# design.net
KiCad netlist of a schematic drawn in Altium Designer
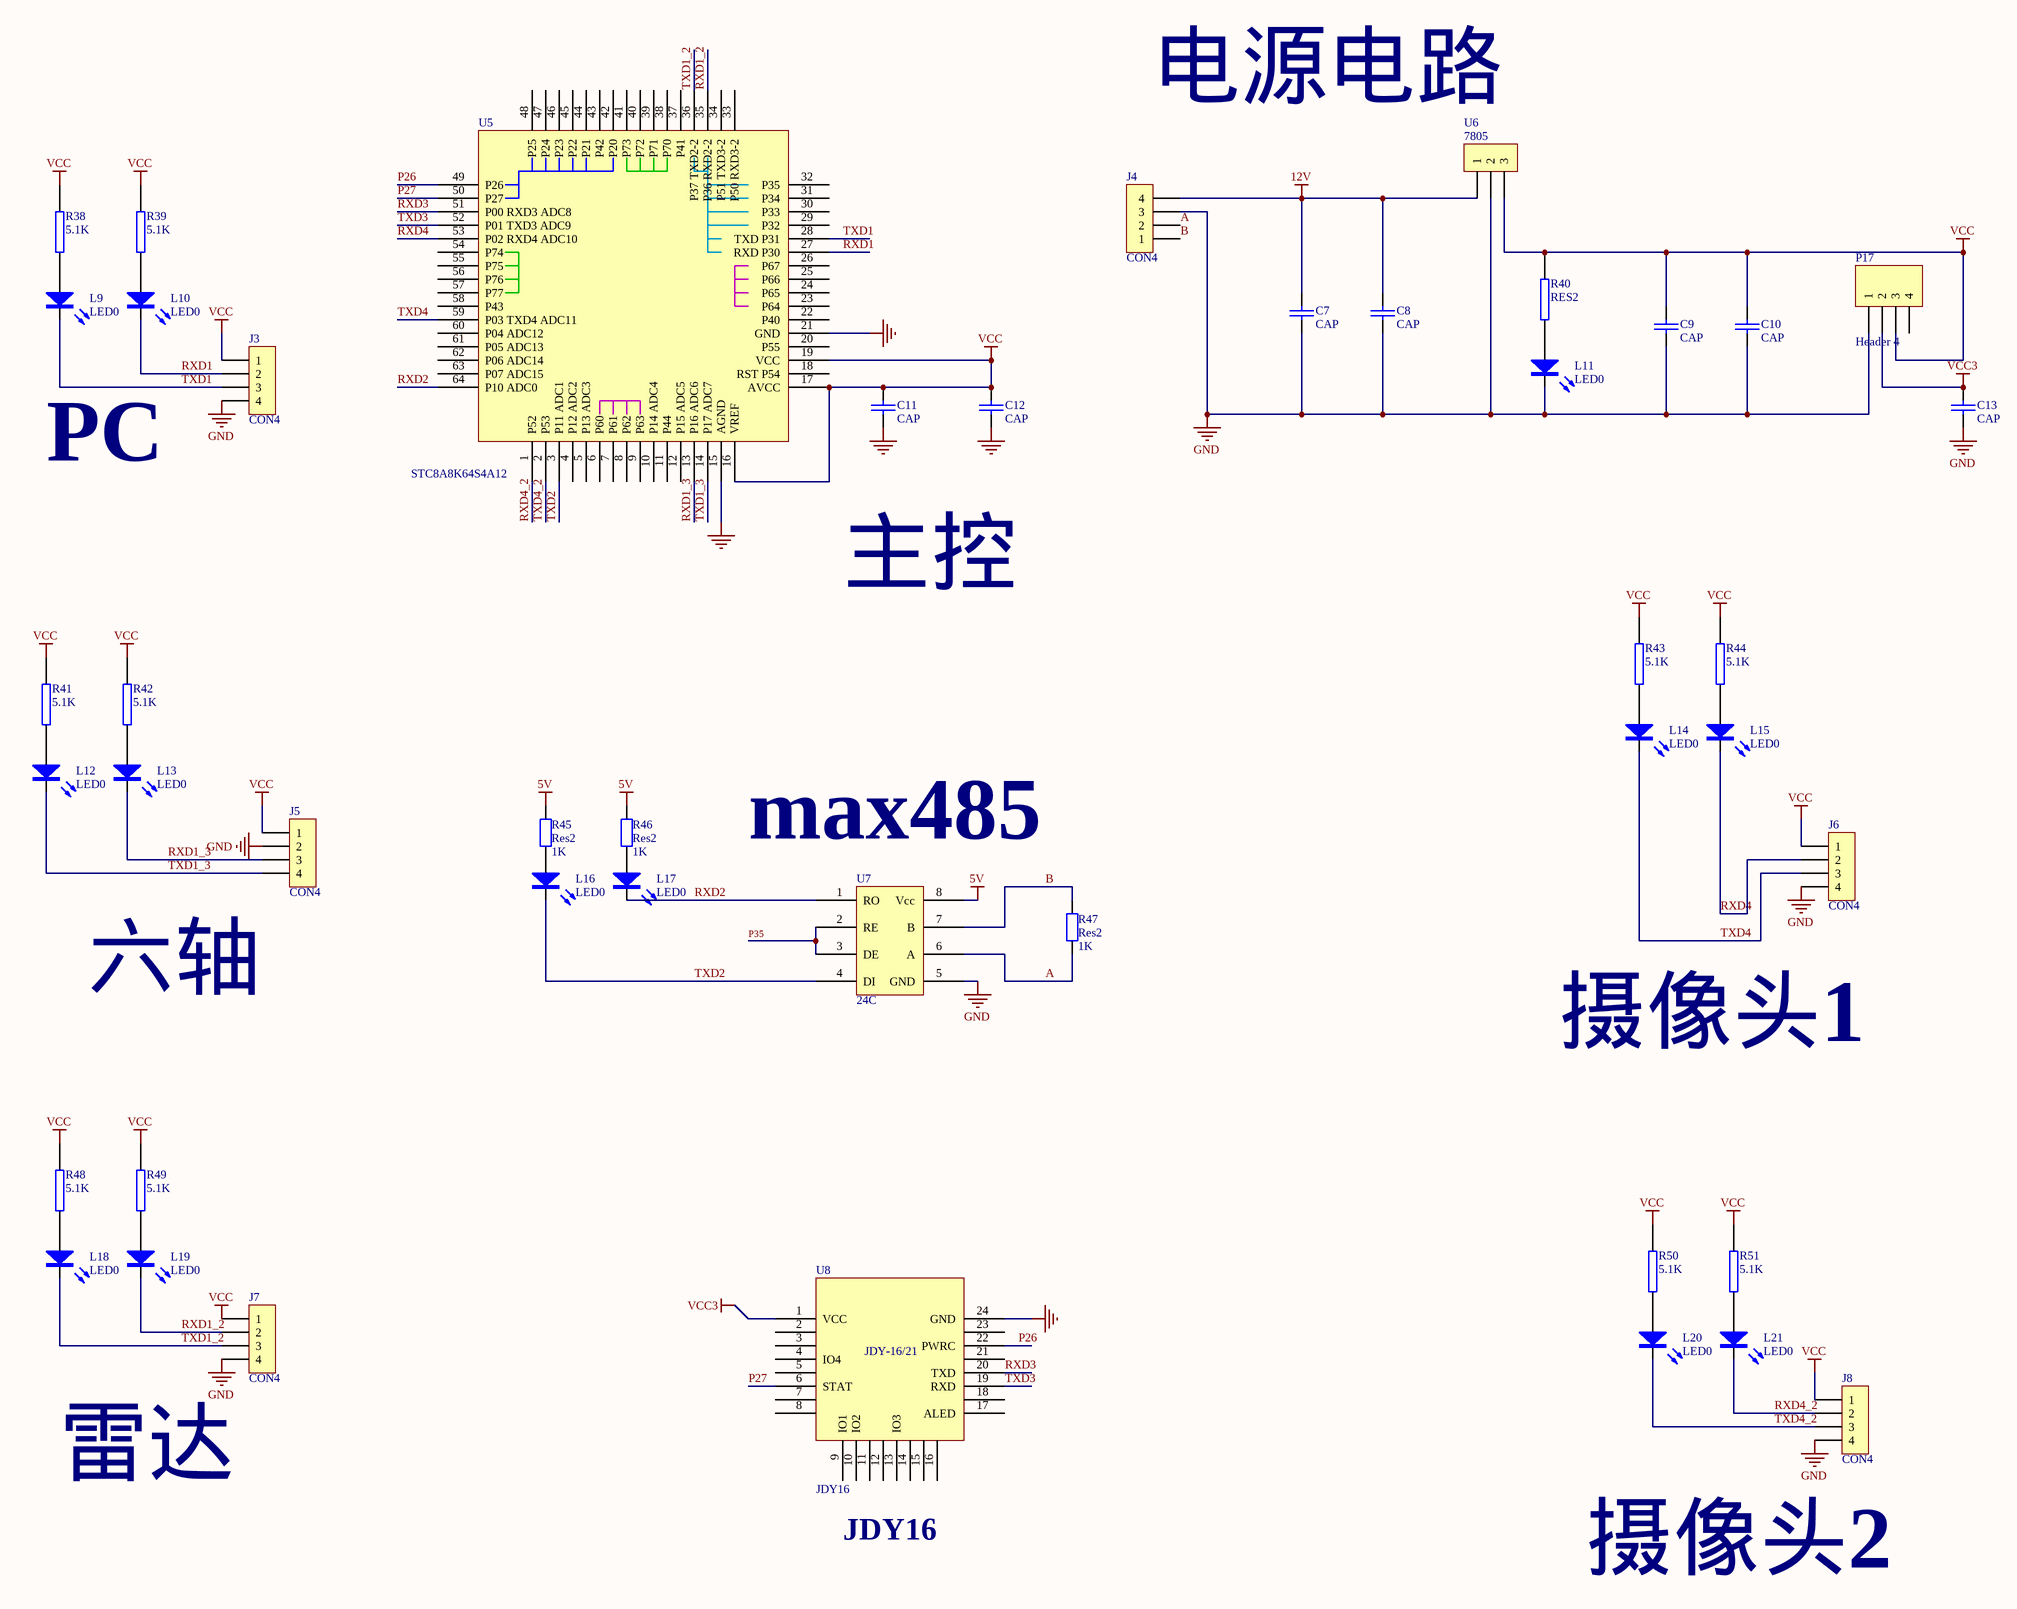
[diagram p0: 扫描仪.SchDoc]

(export (version "E")
  (design (tool "Eeschema 10.0.6"))
  (components
    (comp (ref "C7")
      (value "CAP")
      (footprint "0805_L")
      (description "Capacitor")
      (libsource (lib "*") (part "CAP"))
    )
    (comp (ref "C8")
      (value "CAP")
      (footprint "1206_L")
      (description "Capacitor")
      (libsource (lib "*") (part "CAP"))
    )
    (comp (ref "C9")
      (value "CAP")
      (footprint "0805_L")
      (description "Capacitor")
      (libsource (lib "*") (part "CAP"))
    )
    (comp (ref "C10")
      (value "CAP")
      (footprint "1206_L")
      (description "Capacitor")
      (libsource (lib "*") (part "CAP"))
    )
    (comp (ref "C11")
      (value "CAP")
      (footprint "0805_L")
      (description "Capacitor")
      (libsource (lib "*") (part "CAP"))
    )
    (comp (ref "C12")
      (value "CAP")
      (footprint "0805_L")
      (description "Capacitor")
      (libsource (lib "*") (part "CAP"))
    )
    (comp (ref "C13")
      (value "CAP")
      (footprint "0805_L")
      (description "Capacitor")
      (libsource (lib "*") (part "CAP"))
    )
    (comp (ref "J3")
      (value "CON4")
      (footprint "SP4")
      (description "Connector")
      (libsource (lib "*") (part "CON4"))
    )
    (comp (ref "J4")
      (value "CON4")
      (footprint "SP4")
      (description "Connector")
      (libsource (lib "") (part "CON4_1"))
    )
    (comp (ref "J5")
      (value "CON4")
      (footprint "SP4")
      (description "Connector")
      (libsource (lib "*") (part "CON4"))
    )
    (comp (ref "J6")
      (value "CON4")
      (footprint "SP4")
      (description "Connector")
      (libsource (lib "*") (part "CON4"))
    )
    (comp (ref "J7")
      (value "CON4")
      (footprint "SP4")
      (description "Connector")
      (libsource (lib "*") (part "CON4"))
    )
    (comp (ref "J8")
      (value "CON4")
      (footprint "SP4")
      (description "Connector")
      (libsource (lib "*") (part "CON4"))
    )
    (comp (ref "L9")
      (value "LED0")
      (footprint "TPLED")
      (description "light Emitting Diode")
      (libsource (lib "*") (part "LED0"))
    )
    (comp (ref "L10")
      (value "LED0")
      (footprint "TPLED")
      (description "light Emitting Diode")
      (libsource (lib "*") (part "LED0"))
    )
    (comp (ref "L11")
      (value "LED0")
      (footprint "TPLED")
      (description "light Emitting Diode")
      (libsource (lib "*") (part "LED0"))
    )
    (comp (ref "L12")
      (value "LED0")
      (footprint "TPLED")
      (description "light Emitting Diode")
      (libsource (lib "*") (part "LED0"))
    )
    (comp (ref "L13")
      (value "LED0")
      (footprint "TPLED")
      (description "light Emitting Diode")
      (libsource (lib "*") (part "LED0"))
    )
    (comp (ref "L14")
      (value "LED0")
      (footprint "TPLED")
      (description "light Emitting Diode")
      (libsource (lib "*") (part "LED0"))
    )
    (comp (ref "L15")
      (value "LED0")
      (footprint "TPLED")
      (description "light Emitting Diode")
      (libsource (lib "*") (part "LED0"))
    )
    (comp (ref "L16")
      (value "LED0")
      (footprint "TPLED")
      (description "light Emitting Diode")
      (libsource (lib "*") (part "LED0"))
    )
    (comp (ref "L17")
      (value "LED0")
      (footprint "TPLED")
      (description "light Emitting Diode")
      (libsource (lib "*") (part "LED0"))
    )
    (comp (ref "L18")
      (value "LED0")
      (footprint "TPLED")
      (description "light Emitting Diode")
      (libsource (lib "*") (part "LED0"))
    )
    (comp (ref "L19")
      (value "LED0")
      (footprint "TPLED")
      (description "light Emitting Diode")
      (libsource (lib "*") (part "LED0"))
    )
    (comp (ref "L20")
      (value "LED0")
      (footprint "TPLED")
      (description "light Emitting Diode")
      (libsource (lib "*") (part "LED0"))
    )
    (comp (ref "L21")
      (value "LED0")
      (footprint "TPLED")
      (description "light Emitting Diode")
      (libsource (lib "*") (part "LED0"))
    )
    (comp (ref "P17")
      (value "Header 4")
      (footprint "1117")
      (description "Header, 4-Pin")
      (fields (field (name "PUBLISHER") "Altium Limited"))
      (libsource (lib "Miscellaneous Connectors") (part "Header 4"))
    )
    (comp (ref "R38") (value "5.1K") (footprint "0805_L") (libsource (lib "*") (part "RES2")))
    (comp (ref "R39") (value "5.1K") (footprint "0805_L") (libsource (lib "*") (part "RES2")))
    (comp (ref "R40") (value "RES2") (footprint "0805_L") (libsource (lib "*") (part "RES2")))
    (comp (ref "R41") (value "5.1K") (footprint "0805_L") (libsource (lib "*") (part "RES2")))
    (comp (ref "R42") (value "5.1K") (footprint "0805_L") (libsource (lib "*") (part "RES2")))
    (comp (ref "R43") (value "5.1K") (footprint "0805_L") (libsource (lib "*") (part "RES2")))
    (comp (ref "R44") (value "5.1K") (footprint "0805_L") (libsource (lib "*") (part "RES2")))
    (comp (ref "R45")
      (value "Res2")
      (footprint "0805_R")
      (description "Resistor")
      (fields (field (name "ALTIUM_VALUE") "1K") (field (name "PUBLISHER") "Altium Limited"))
      (libsource (lib "Miscellaneous Devices") (part "Res2"))
    )
    (comp (ref "R46")
      (value "Res2")
      (footprint "0805_R")
      (description "Resistor")
      (fields (field (name "ALTIUM_VALUE") "1K") (field (name "PUBLISHER") "Altium Limited"))
      (libsource (lib "Miscellaneous Devices") (part "Res2"))
    )
    (comp (ref "R47")
      (value "Res2")
      (footprint "0805_R")
      (description "Resistor")
      (fields (field (name "ALTIUM_VALUE") "1K") (field (name "PUBLISHER") "Altium Limited"))
      (libsource (lib "Miscellaneous Devices") (part "Res2"))
    )
    (comp (ref "R48") (value "5.1K") (footprint "0805_L") (libsource (lib "*") (part "RES2")))
    (comp (ref "R49") (value "5.1K") (footprint "0805_L") (libsource (lib "*") (part "RES2")))
    (comp (ref "R50") (value "5.1K") (footprint "0805_L") (libsource (lib "*") (part "RES2")))
    (comp (ref "R51") (value "5.1K") (footprint "0805_L") (libsource (lib "*") (part "RES2")))
    (comp (ref "U5") (value "STC8A8K64S4A12") (footprint "LQFP64S") (libsource (lib "*") (part "STC64")))
    (comp (ref "U6")
      (value "7805")
      (footprint "TO252")
      (description "Connector")
      (libsource (lib "*") (part "CON3"))
    )
    (comp (ref "U7") (value "24C") (footprint "SOP8") (libsource (lib "*") (part "24C")))
    (comp (ref "U8") (value "JDY16") (footprint "JDY16") (libsource (lib "stc64") (part "JDY21")))
  )
  (nets
    (net (code "1") (name "/A") (class "Default")
      (node (ref "J4") (pin "2") (pinfunction "2_2") (pintype "passive"))
      (node (ref "R47") (pin "1") (pinfunction "1_1") (pintype "passive"))
      (node (ref "U7") (pin "6") (pinfunction "A_6") (pintype "passive"))
    )
    (net (code "2") (name "/B") (class "Default")
      (node (ref "J4") (pin "1") (pinfunction "1_1") (pintype "passive"))
      (node (ref "R47") (pin "2") (pinfunction "2_2") (pintype "passive"))
      (node (ref "U7") (pin "7") (pinfunction "B_7") (pintype "passive"))
    )
    (net (code "3") (name "/P26") (class "Default")
      (node (ref "U5") (pin "49") (pinfunction "P26_49") (pintype "passive"))
      (node (ref "U8") (pin "22") (pinfunction "PWRC_22") (pintype "passive"))
    )
    (net (code "4") (name "/P27") (class "Default")
      (node (ref "U5") (pin "50") (pinfunction "P27_50") (pintype "passive"))
      (node (ref "U8") (pin "6") (pinfunction "STAT_6") (pintype "passive"))
    )
    (net (code "5") (name "/P35") (class "Default")
      (node (ref "U7") (pin "2") (pinfunction "RE_2") (pintype "passive"))
      (node (ref "U7") (pin "3") (pinfunction "DE_3") (pintype "passive"))
    )
    (net (code "6") (name "/RXD1") (class "Default")
      (node (ref "J3") (pin "2") (pinfunction "2_2") (pintype "passive"))
      (node (ref "L10") (pin "2") (pinfunction "K_2") (pintype "passive"))
      (node (ref "U5") (pin "27") (pinfunction "RXD_P30_27") (pintype "passive"))
    )
    (net (code "7") (name "/RXD1_2") (class "Default")
      (node (ref "J7") (pin "2") (pinfunction "2_2") (pintype "passive"))
      (node (ref "L19") (pin "2") (pinfunction "K_2") (pintype "passive"))
      (node (ref "U5") (pin "35") (pinfunction "P36_RXD2-2_35") (pintype "passive"))
    )
    (net (code "8") (name "/RXD1_3") (class "Default")
      (node (ref "J5") (pin "3") (pinfunction "3_3") (pintype "passive"))
      (node (ref "L13") (pin "2") (pinfunction "K_2") (pintype "passive"))
      (node (ref "U5") (pin "13") (pinfunction "P16_ADC6_13") (pintype "passive"))
    )
    (net (code "9") (name "/RXD2") (class "Default")
      (node (ref "L17") (pin "2") (pinfunction "K_2") (pintype "passive"))
      (node (ref "U5") (pin "64") (pinfunction "P10_ADC0_64") (pintype "passive"))
      (node (ref "U7") (pin "1") (pinfunction "RO_1") (pintype "passive"))
    )
    (net (code "10") (name "/RXD3") (class "Default")
      (node (ref "U5") (pin "51") (pinfunction "P00_RXD3_ADC8_51") (pintype "passive"))
      (node (ref "U8") (pin "20") (pinfunction "TXD_20") (pintype "passive"))
    )
    (net (code "11") (name "/RXD4") (class "Default")
      (node (ref "J6") (pin "2") (pinfunction "2_2") (pintype "passive"))
      (node (ref "L15") (pin "2") (pinfunction "K_2") (pintype "passive"))
      (node (ref "U5") (pin "53") (pinfunction "P02_RXD4_ADC10_53") (pintype "passive"))
    )
    (net (code "12") (name "/RXD4_2") (class "Default")
      (node (ref "J8") (pin "2") (pinfunction "2_2") (pintype "passive"))
      (node (ref "L21") (pin "2") (pinfunction "K_2") (pintype "passive"))
      (node (ref "U5") (pin "1") (pinfunction "P52_1") (pintype "passive"))
    )
    (net (code "13") (name "/TXD1") (class "Default")
      (node (ref "J3") (pin "3") (pinfunction "3_3") (pintype "passive"))
      (node (ref "L9") (pin "2") (pinfunction "K_2") (pintype "passive"))
      (node (ref "U5") (pin "28") (pinfunction "TXD_P31_28") (pintype "passive"))
    )
    (net (code "14") (name "/TXD1_2") (class "Default")
      (node (ref "J7") (pin "3") (pinfunction "3_3") (pintype "passive"))
      (node (ref "L18") (pin "2") (pinfunction "K_2") (pintype "passive"))
      (node (ref "U5") (pin "36") (pinfunction "P37_TXD2-2_36") (pintype "passive"))
    )
    (net (code "15") (name "/TXD1_3") (class "Default")
      (node (ref "J5") (pin "4") (pinfunction "4_4") (pintype "passive"))
      (node (ref "L12") (pin "2") (pinfunction "K_2") (pintype "passive"))
      (node (ref "U5") (pin "14") (pinfunction "P17_ADC7_14") (pintype "passive"))
    )
    (net (code "16") (name "/TXD2") (class "Default")
      (node (ref "L16") (pin "2") (pinfunction "K_2") (pintype "passive"))
      (node (ref "U5") (pin "3") (pinfunction "P11_ADC1_3") (pintype "passive"))
      (node (ref "U7") (pin "4") (pinfunction "DI_4") (pintype "passive"))
    )
    (net (code "17") (name "/TXD3") (class "Default")
      (node (ref "U5") (pin "52") (pinfunction "P01_TXD3_ADC9_52") (pintype "passive"))
      (node (ref "U8") (pin "19") (pinfunction "RXD_19") (pintype "passive"))
    )
    (net (code "18") (name "/TXD4") (class "Default")
      (node (ref "J6") (pin "3") (pinfunction "3_3") (pintype "passive"))
      (node (ref "L14") (pin "2") (pinfunction "K_2") (pintype "passive"))
      (node (ref "U5") (pin "59") (pinfunction "P03_TXD4_ADC11_59") (pintype "passive"))
    )
    (net (code "19") (name "/TXD4_2") (class "Default")
      (node (ref "J8") (pin "3") (pinfunction "3_3") (pintype "passive"))
      (node (ref "L20") (pin "2") (pinfunction "K_2") (pintype "passive"))
      (node (ref "U5") (pin "2") (pinfunction "P53_2") (pintype "passive"))
    )
    (net (code "20") (name "5V") (class "Default")
      (node (ref "R45") (pin "2") (pinfunction "2_2") (pintype "passive"))
      (node (ref "R46") (pin "2") (pinfunction "2_2") (pintype "passive"))
      (node (ref "U7") (pin "8") (pinfunction "Vcc_8") (pintype "passive"))
    )
    (net (code "21") (name "12V") (class "Default")
      (node (ref "C7") (pin "1") (pinfunction "1_1") (pintype "passive"))
      (node (ref "C8") (pin "1") (pinfunction "1_1") (pintype "passive"))
      (node (ref "J4") (pin "4") (pinfunction "4_4") (pintype "passive"))
      (node (ref "U6") (pin "1") (pinfunction "1_1") (pintype "passive"))
    )
    (net (code "22") (name "GND") (class "Default")
      (node (ref "C10") (pin "2") (pinfunction "2_2") (pintype "passive"))
      (node (ref "C11") (pin "2") (pinfunction "2_2") (pintype "passive"))
      (node (ref "C12") (pin "2") (pinfunction "2_2") (pintype "passive"))
      (node (ref "C13") (pin "2") (pinfunction "2_2") (pintype "passive"))
      (node (ref "C7") (pin "2") (pinfunction "2_2") (pintype "passive"))
      (node (ref "C8") (pin "2") (pinfunction "2_2") (pintype "passive"))
      (node (ref "C9") (pin "2") (pinfunction "2_2") (pintype "passive"))
      (node (ref "J3") (pin "4") (pinfunction "4_4") (pintype "passive"))
      (node (ref "J4") (pin "3") (pinfunction "3_3") (pintype "passive"))
      (node (ref "J5") (pin "2") (pinfunction "2_2") (pintype "passive"))
      (node (ref "J6") (pin "4") (pinfunction "4_4") (pintype "passive"))
      (node (ref "J7") (pin "4") (pinfunction "4_4") (pintype "passive"))
      (node (ref "J8") (pin "4") (pinfunction "4_4") (pintype "passive"))
      (node (ref "L11") (pin "2") (pinfunction "K_2") (pintype "passive"))
      (node (ref "P17") (pin "1") (pinfunction "1_1") (pintype "passive"))
      (node (ref "U5") (pin "15") (pinfunction "AGND_15") (pintype "passive"))
      (node (ref "U5") (pin "21") (pinfunction "GND_21") (pintype "passive"))
      (node (ref "U6") (pin "2") (pinfunction "2_2") (pintype "passive"))
      (node (ref "U7") (pin "5") (pinfunction "GND_5") (pintype "passive"))
      (node (ref "U8") (pin "24") (pinfunction "GND_24") (pintype "passive"))
    )
    (net (code "23") (name "Net-(L9-A)") (class "Default")
      (node (ref "L9") (pin "1") (pinfunction "A_1") (pintype "passive"))
      (node (ref "R38") (pin "1") (pinfunction "1_1") (pintype "passive"))
    )
    (net (code "24") (name "Net-(L10-A)") (class "Default")
      (node (ref "L10") (pin "1") (pinfunction "A_1") (pintype "passive"))
      (node (ref "R39") (pin "1") (pinfunction "1_1") (pintype "passive"))
    )
    (net (code "25") (name "Net-(L11-A)") (class "Default")
      (node (ref "L11") (pin "1") (pinfunction "A_1") (pintype "passive"))
      (node (ref "R40") (pin "1") (pinfunction "1_1") (pintype "passive"))
    )
    (net (code "26") (name "Net-(L12-A)") (class "Default")
      (node (ref "L12") (pin "1") (pinfunction "A_1") (pintype "passive"))
      (node (ref "R41") (pin "1") (pinfunction "1_1") (pintype "passive"))
    )
    (net (code "27") (name "Net-(L13-A)") (class "Default")
      (node (ref "L13") (pin "1") (pinfunction "A_1") (pintype "passive"))
      (node (ref "R42") (pin "1") (pinfunction "1_1") (pintype "passive"))
    )
    (net (code "28") (name "Net-(L14-A)") (class "Default")
      (node (ref "L14") (pin "1") (pinfunction "A_1") (pintype "passive"))
      (node (ref "R43") (pin "1") (pinfunction "1_1") (pintype "passive"))
    )
    (net (code "29") (name "Net-(L15-A)") (class "Default")
      (node (ref "L15") (pin "1") (pinfunction "A_1") (pintype "passive"))
      (node (ref "R44") (pin "1") (pinfunction "1_1") (pintype "passive"))
    )
    (net (code "30") (name "Net-(L16-A)") (class "Default")
      (node (ref "L16") (pin "1") (pinfunction "A_1") (pintype "passive"))
      (node (ref "R45") (pin "1") (pinfunction "1_1") (pintype "passive"))
    )
    (net (code "31") (name "Net-(L17-A)") (class "Default")
      (node (ref "L17") (pin "1") (pinfunction "A_1") (pintype "passive"))
      (node (ref "R46") (pin "1") (pinfunction "1_1") (pintype "passive"))
    )
    (net (code "32") (name "Net-(L18-A)") (class "Default")
      (node (ref "L18") (pin "1") (pinfunction "A_1") (pintype "passive"))
      (node (ref "R48") (pin "1") (pinfunction "1_1") (pintype "passive"))
    )
    (net (code "33") (name "Net-(L19-A)") (class "Default")
      (node (ref "L19") (pin "1") (pinfunction "A_1") (pintype "passive"))
      (node (ref "R49") (pin "1") (pinfunction "1_1") (pintype "passive"))
    )
    (net (code "34") (name "Net-(L20-A)") (class "Default")
      (node (ref "L20") (pin "1") (pinfunction "A_1") (pintype "passive"))
      (node (ref "R50") (pin "1") (pinfunction "1_1") (pintype "passive"))
    )
    (net (code "35") (name "Net-(L21-A)") (class "Default")
      (node (ref "L21") (pin "1") (pinfunction "A_1") (pintype "passive"))
      (node (ref "R51") (pin "1") (pinfunction "1_1") (pintype "passive"))
    )
    (net (code "36") (name "VCC") (class "Default")
      (node (ref "C10") (pin "1") (pinfunction "1_1") (pintype "passive"))
      (node (ref "C11") (pin "1") (pinfunction "1_1") (pintype "passive"))
      (node (ref "C12") (pin "1") (pinfunction "1_1") (pintype "passive"))
      (node (ref "C9") (pin "1") (pinfunction "1_1") (pintype "passive"))
      (node (ref "J3") (pin "1") (pinfunction "1_1") (pintype "passive"))
      (node (ref "J5") (pin "1") (pinfunction "1_1") (pintype "passive"))
      (node (ref "J6") (pin "1") (pinfunction "1_1") (pintype "passive"))
      (node (ref "J7") (pin "1") (pinfunction "1_1") (pintype "passive"))
      (node (ref "J8") (pin "1") (pinfunction "1_1") (pintype "passive"))
      (node (ref "P17") (pin "3") (pinfunction "3_3") (pintype "passive"))
      (node (ref "R38") (pin "2") (pinfunction "2_2") (pintype "passive"))
      (node (ref "R39") (pin "2") (pinfunction "2_2") (pintype "passive"))
      (node (ref "R40") (pin "2") (pinfunction "2_2") (pintype "passive"))
      (node (ref "R41") (pin "2") (pinfunction "2_2") (pintype "passive"))
      (node (ref "R42") (pin "2") (pinfunction "2_2") (pintype "passive"))
      (node (ref "R43") (pin "2") (pinfunction "2_2") (pintype "passive"))
      (node (ref "R44") (pin "2") (pinfunction "2_2") (pintype "passive"))
      (node (ref "R48") (pin "2") (pinfunction "2_2") (pintype "passive"))
      (node (ref "R49") (pin "2") (pinfunction "2_2") (pintype "passive"))
      (node (ref "R50") (pin "2") (pinfunction "2_2") (pintype "passive"))
      (node (ref "R51") (pin "2") (pinfunction "2_2") (pintype "passive"))
      (node (ref "U5") (pin "16") (pinfunction "VREF_16") (pintype "passive"))
      (node (ref "U5") (pin "17") (pinfunction "AVCC_17") (pintype "passive"))
      (node (ref "U5") (pin "19") (pinfunction "VCC_19") (pintype "passive"))
      (node (ref "U6") (pin "3") (pinfunction "3_3") (pintype "passive"))
    )
    (net (code "37") (name "VCC3") (class "Default")
      (node (ref "C13") (pin "1") (pinfunction "1_1") (pintype "passive"))
      (node (ref "P17") (pin "2") (pinfunction "2_2") (pintype "passive"))
      (node (ref "U8") (pin "1") (pinfunction "VCC_1") (pintype "passive"))
    )
    (net (code "38") (name "unconnected-(P17-Pad4)") (class "Default")
      (node (ref "P17") (pin "4") (pinfunction "4_4") (pintype "passive"))
    )
    (net (code "39") (name "unconnected-(U5-P04_ADC12-Pad60)") (class "Default")
      (node (ref "U5") (pin "60") (pinfunction "P04_ADC12_60") (pintype "passive"))
    )
    (net (code "40") (name "unconnected-(U5-P05_ADC13-Pad61)") (class "Default")
      (node (ref "U5") (pin "61") (pinfunction "P05_ADC13_61") (pintype "passive"))
    )
    (net (code "41") (name "unconnected-(U5-P06_ADC14-Pad62)") (class "Default")
      (node (ref "U5") (pin "62") (pinfunction "P06_ADC14_62") (pintype "passive"))
    )
    (net (code "42") (name "unconnected-(U5-P07_ADC15-Pad63)") (class "Default")
      (node (ref "U5") (pin "63") (pinfunction "P07_ADC15_63") (pintype "passive"))
    )
    (net (code "43") (name "unconnected-(U5-P12_ADC2-Pad4)") (class "Default")
      (node (ref "U5") (pin "4") (pinfunction "P12_ADC2_4") (pintype "passive"))
    )
    (net (code "44") (name "unconnected-(U5-P13_ADC3-Pad5)") (class "Default")
      (node (ref "U5") (pin "5") (pinfunction "P13_ADC3_5") (pintype "passive"))
    )
    (net (code "45") (name "unconnected-(U5-P14_ADC4-Pad10)") (class "Default")
      (node (ref "U5") (pin "10") (pinfunction "P14_ADC4_10") (pintype "passive"))
    )
    (net (code "46") (name "unconnected-(U5-P15_ADC5-Pad12)") (class "Default")
      (node (ref "U5") (pin "12") (pinfunction "P15_ADC5_12") (pintype "passive"))
    )
    (net (code "47") (name "unconnected-(U5-P20-Pad42)") (class "Default")
      (node (ref "U5") (pin "42") (pinfunction "P20_42") (pintype "passive"))
    )
    (net (code "48") (name "unconnected-(U5-P21-Pad44)") (class "Default")
      (node (ref "U5") (pin "44") (pinfunction "P21_44") (pintype "passive"))
    )
    (net (code "49") (name "unconnected-(U5-P22-Pad45)") (class "Default")
      (node (ref "U5") (pin "45") (pinfunction "P22_45") (pintype "passive"))
    )
    (net (code "50") (name "unconnected-(U5-P23-Pad46)") (class "Default")
      (node (ref "U5") (pin "46") (pinfunction "P23_46") (pintype "passive"))
    )
    (net (code "51") (name "unconnected-(U5-P24-Pad47)") (class "Default")
      (node (ref "U5") (pin "47") (pinfunction "P24_47") (pintype "passive"))
    )
    (net (code "52") (name "unconnected-(U5-P25-Pad48)") (class "Default")
      (node (ref "U5") (pin "48") (pinfunction "P25_48") (pintype "passive"))
    )
    (net (code "53") (name "unconnected-(U5-P32-Pad29)") (class "Default")
      (node (ref "U5") (pin "29") (pinfunction "P32_29") (pintype "passive"))
    )
    (net (code "54") (name "unconnected-(U5-P33-Pad30)") (class "Default")
      (node (ref "U5") (pin "30") (pinfunction "P33_30") (pintype "passive"))
    )
    (net (code "55") (name "unconnected-(U5-P34-Pad31)") (class "Default")
      (node (ref "U5") (pin "31") (pinfunction "P34_31") (pintype "passive"))
    )
    (net (code "56") (name "unconnected-(U5-P35-Pad32)") (class "Default")
      (node (ref "U5") (pin "32") (pinfunction "P35_32") (pintype "passive"))
    )
    (net (code "57") (name "unconnected-(U5-P40-Pad22)") (class "Default")
      (node (ref "U5") (pin "22") (pinfunction "P40_22") (pintype "passive"))
    )
    (net (code "58") (name "unconnected-(U5-P41-Pad37)") (class "Default")
      (node (ref "U5") (pin "37") (pinfunction "P41_37") (pintype "passive"))
    )
    (net (code "59") (name "unconnected-(U5-P42-Pad43)") (class "Default")
      (node (ref "U5") (pin "43") (pinfunction "P42_43") (pintype "passive"))
    )
    (net (code "60") (name "unconnected-(U5-P43-Pad58)") (class "Default")
      (node (ref "U5") (pin "58") (pinfunction "P43_58") (pintype "passive"))
    )
    (net (code "61") (name "unconnected-(U5-P44-Pad11)") (class "Default")
      (node (ref "U5") (pin "11") (pinfunction "P44_11") (pintype "passive"))
    )
    (net (code "62") (name "unconnected-(U5-P50_RXD3-2-Pad33)") (class "Default")
      (node (ref "U5") (pin "33") (pinfunction "P50_RXD3-2_33") (pintype "passive"))
    )
    (net (code "63") (name "unconnected-(U5-P51_TXD3-2-Pad34)") (class "Default")
      (node (ref "U5") (pin "34") (pinfunction "P51_TXD3-2_34") (pintype "passive"))
    )
    (net (code "64") (name "unconnected-(U5-P55-Pad20)") (class "Default")
      (node (ref "U5") (pin "20") (pinfunction "P55_20") (pintype "passive"))
    )
    (net (code "65") (name "unconnected-(U5-P60-Pad6)") (class "Default")
      (node (ref "U5") (pin "6") (pinfunction "P60_6") (pintype "passive"))
    )
    (net (code "66") (name "unconnected-(U5-P61-Pad7)") (class "Default")
      (node (ref "U5") (pin "7") (pinfunction "P61_7") (pintype "passive"))
    )
    (net (code "67") (name "unconnected-(U5-P62-Pad8)") (class "Default")
      (node (ref "U5") (pin "8") (pinfunction "P62_8") (pintype "passive"))
    )
    (net (code "68") (name "unconnected-(U5-P63-Pad9)") (class "Default")
      (node (ref "U5") (pin "9") (pinfunction "P63_9") (pintype "passive"))
    )
    (net (code "69") (name "unconnected-(U5-P64-Pad23)") (class "Default")
      (node (ref "U5") (pin "23") (pinfunction "P64_23") (pintype "passive"))
    )
    (net (code "70") (name "unconnected-(U5-P65-Pad24)") (class "Default")
      (node (ref "U5") (pin "24") (pinfunction "P65_24") (pintype "passive"))
    )
    (net (code "71") (name "unconnected-(U5-P66-Pad25)") (class "Default")
      (node (ref "U5") (pin "25") (pinfunction "P66_25") (pintype "passive"))
    )
    (net (code "72") (name "unconnected-(U5-P67-Pad26)") (class "Default")
      (node (ref "U5") (pin "26") (pinfunction "P67_26") (pintype "passive"))
    )
    (net (code "73") (name "unconnected-(U5-P70-Pad38)") (class "Default")
      (node (ref "U5") (pin "38") (pinfunction "P70_38") (pintype "passive"))
    )
    (net (code "74") (name "unconnected-(U5-P71-Pad39)") (class "Default")
      (node (ref "U5") (pin "39") (pinfunction "P71_39") (pintype "passive"))
    )
    (net (code "75") (name "unconnected-(U5-P72-Pad40)") (class "Default")
      (node (ref "U5") (pin "40") (pinfunction "P72_40") (pintype "passive"))
    )
    (net (code "76") (name "unconnected-(U5-P73-Pad41)") (class "Default")
      (node (ref "U5") (pin "41") (pinfunction "P73_41") (pintype "passive"))
    )
    (net (code "77") (name "unconnected-(U5-P74-Pad54)") (class "Default")
      (node (ref "U5") (pin "54") (pinfunction "P74_54") (pintype "passive"))
    )
    (net (code "78") (name "unconnected-(U5-P75-Pad55)") (class "Default")
      (node (ref "U5") (pin "55") (pinfunction "P75_55") (pintype "passive"))
    )
    (net (code "79") (name "unconnected-(U5-P76-Pad56)") (class "Default")
      (node (ref "U5") (pin "56") (pinfunction "P76_56") (pintype "passive"))
    )
    (net (code "80") (name "unconnected-(U5-P77-Pad57)") (class "Default")
      (node (ref "U5") (pin "57") (pinfunction "P77_57") (pintype "passive"))
    )
    (net (code "81") (name "unconnected-(U5-RST_P54-Pad18)") (class "Default")
      (node (ref "U5") (pin "18") (pinfunction "RST_P54_18") (pintype "passive"))
    )
    (net (code "82") (name "unconnected-(U8-ALED-Pad17)") (class "Default")
      (node (ref "U8") (pin "17") (pinfunction "ALED_17") (pintype "passive"))
    )
    (net (code "83") (name "unconnected-(U8-IO1-Pad9)") (class "Default")
      (node (ref "U8") (pin "9") (pinfunction "IO1_9") (pintype "passive"))
    )
    (net (code "84") (name "unconnected-(U8-IO2-Pad10)") (class "Default")
      (node (ref "U8") (pin "10") (pinfunction "IO2_10") (pintype "passive"))
    )
    (net (code "85") (name "unconnected-(U8-IO3-Pad13)") (class "Default")
      (node (ref "U8") (pin "13") (pinfunction "IO3_13") (pintype "passive"))
    )
    (net (code "86") (name "unconnected-(U8-IO4-Pad4)") (class "Default")
      (node (ref "U8") (pin "4") (pinfunction "IO4_4") (pintype "passive"))
    )
    (net (code "87") (name "unconnected-(U8-Pad2)") (class "Default")
      (node (ref "U8") (pin "2") (pintype "passive"))
    )
    (net (code "88") (name "unconnected-(U8-Pad3)") (class "Default")
      (node (ref "U8") (pin "3") (pintype "passive"))
    )
    (net (code "89") (name "unconnected-(U8-Pad5)") (class "Default")
      (node (ref "U8") (pin "5") (pintype "passive"))
    )
    (net (code "90") (name "unconnected-(U8-Pad7)") (class "Default")
      (node (ref "U8") (pin "7") (pintype "passive"))
    )
    (net (code "91") (name "unconnected-(U8-Pad8)") (class "Default")
      (node (ref "U8") (pin "8") (pintype "passive"))
    )
    (net (code "92") (name "unconnected-(U8-Pad11)") (class "Default")
      (node (ref "U8") (pin "11") (pintype "passive"))
    )
    (net (code "93") (name "unconnected-(U8-Pad12)") (class "Default")
      (node (ref "U8") (pin "12") (pintype "passive"))
    )
    (net (code "94") (name "unconnected-(U8-Pad14)") (class "Default")
      (node (ref "U8") (pin "14") (pintype "passive"))
    )
    (net (code "95") (name "unconnected-(U8-Pad15)") (class "Default")
      (node (ref "U8") (pin "15") (pintype "passive"))
    )
    (net (code "96") (name "unconnected-(U8-Pad16)") (class "Default")
      (node (ref "U8") (pin "16") (pintype "passive"))
    )
    (net (code "97") (name "unconnected-(U8-Pad18)") (class "Default")
      (node (ref "U8") (pin "18") (pintype "passive"))
    )
    (net (code "98") (name "unconnected-(U8-Pad21)") (class "Default")
      (node (ref "U8") (pin "21") (pintype "passive"))
    )
    (net (code "99") (name "unconnected-(U8-Pad23)") (class "Default")
      (node (ref "U8") (pin "23") (pintype "passive"))
    )
  )
)
